# Treiber_01.net
KiCad netlist of a schematic drawn in EAGLE
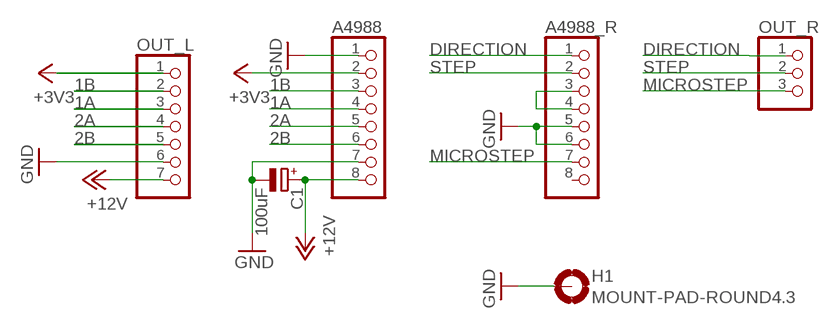
[diagram p0: schematic, sheet 1]

(export (version "E")
  (design (tool "Eeschema 10.0.6"))
  (components
    (comp (ref "A4988")
      (value "PINHD-1X8")
      (footprint "eagle-import:1X08")
      (libsource (lib "eagle-import") (part "PINHD-1X8"))
    )
    (comp (ref "A4988_R")
      (value "PINHD-1X8")
      (footprint "eagle-import:1X08")
      (libsource (lib "eagle-import") (part "PINHD-1X8"))
    )
    (comp (ref "C1")
      (value "100uF")
      (footprint "eagle-import:E3,5-8")
      (libsource (lib "eagle-import") (part "CPOL-EUE3.5-8"))
    )
    (comp (ref "H1")
      (value "MOUNT-PAD-ROUND4.3")
      (footprint "eagle-import:4,3-PAD")
      (libsource (lib "eagle-import") (part "MOUNT-PAD-ROUND4.3"))
    )
    (comp (ref "OUT_L")
      (value "PINHD-1X7")
      (footprint "eagle-import:1X07")
      (libsource (lib "eagle-import") (part "PINHD-1X7"))
    )
    (comp (ref "OUT_R")
      (value "PINHD-1X3")
      (footprint "eagle-import:1X03")
      (libsource (lib "eagle-import") (part "PINHD-1X3"))
    )
  )
  (nets
    (net (code "1") (name "+3V3") (class "Default")
      (node (ref "A4988") (pin "2") (pinfunction "2_2") (pintype "passive"))
      (node (ref "OUT_L") (pin "1") (pinfunction "1_1") (pintype "passive"))
    )
    (net (code "2") (name "+12V") (class "Default")
      (node (ref "A4988") (pin "8") (pinfunction "8_8") (pintype "passive"))
      (node (ref "C1") (pin "+") (pinfunction "+_+") (pintype "passive"))
      (node (ref "OUT_L") (pin "7") (pinfunction "7_7") (pintype "passive"))
    )
    (net (code "3") (name "/1A") (class "Default")
      (node (ref "A4988") (pin "4") (pinfunction "4_4") (pintype "passive"))
      (node (ref "OUT_L") (pin "3") (pinfunction "3_3") (pintype "passive"))
    )
    (net (code "4") (name "/1B") (class "Default")
      (node (ref "A4988") (pin "3") (pinfunction "3_3") (pintype "passive"))
      (node (ref "OUT_L") (pin "2") (pinfunction "2_2") (pintype "passive"))
    )
    (net (code "5") (name "/2A") (class "Default")
      (node (ref "A4988") (pin "5") (pinfunction "5_5") (pintype "passive"))
      (node (ref "OUT_L") (pin "4") (pinfunction "4_4") (pintype "passive"))
    )
    (net (code "6") (name "/2B") (class "Default")
      (node (ref "A4988") (pin "6") (pinfunction "6_6") (pintype "passive"))
      (node (ref "OUT_L") (pin "5") (pinfunction "5_5") (pintype "passive"))
    )
    (net (code "7") (name "/DIRECTION") (class "Default")
      (node (ref "A4988_R") (pin "1") (pinfunction "1_1") (pintype "passive"))
      (node (ref "OUT_R") (pin "1") (pinfunction "1_1") (pintype "passive"))
    )
    (net (code "8") (name "/MICROSTEP") (class "Default")
      (node (ref "A4988_R") (pin "7") (pinfunction "7_7") (pintype "passive"))
      (node (ref "OUT_R") (pin "3") (pinfunction "3_3") (pintype "passive"))
    )
    (net (code "9") (name "/STEP") (class "Default")
      (node (ref "A4988_R") (pin "2") (pinfunction "2_2") (pintype "passive"))
      (node (ref "OUT_R") (pin "2") (pinfunction "2_2") (pintype "passive"))
    )
    (net (code "10") (name "GND") (class "Default")
      (node (ref "A4988") (pin "1") (pinfunction "1_1") (pintype "passive"))
      (node (ref "A4988") (pin "7") (pinfunction "7_7") (pintype "passive"))
      (node (ref "A4988_R") (pin "5") (pinfunction "5_5") (pintype "passive"))
      (node (ref "A4988_R") (pin "6") (pinfunction "6_6") (pintype "passive"))
      (node (ref "C1") (pin "-") (pinfunction "-_-") (pintype "passive"))
      (node (ref "H1") (pin "B4,3") (pinfunction "MOUNT_B4,3") (pintype "passive"))
      (node (ref "OUT_L") (pin "6") (pinfunction "6_6") (pintype "passive"))
    )
    (net (code "11") (name "Net-(A4988_R-Pad3)") (class "Default")
      (node (ref "A4988_R") (pin "3") (pinfunction "3_3") (pintype "passive"))
      (node (ref "A4988_R") (pin "4") (pinfunction "4_4") (pintype "passive"))
    )
    (net (code "12") (name "unconnected-(A4988_R-Pad8)") (class "Default")
      (node (ref "A4988_R") (pin "8") (pinfunction "8_8") (pintype "passive"))
    )
  )
)
